# main.net
KiCad netlist of a schematic drawn in EAGLE
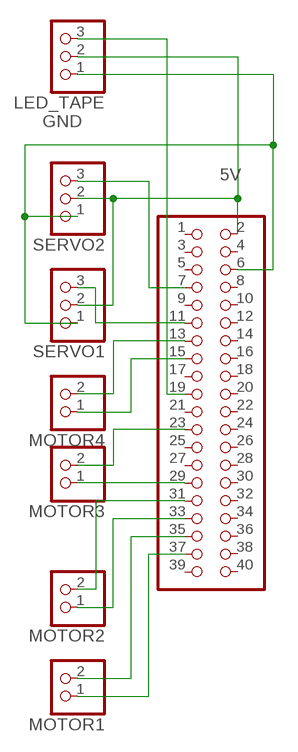
[diagram p0: schematic, sheet 1]

(export (version "E")
  (design (tool "Eeschema 10.0.6"))
  (components
    (comp (ref "JP")
      (value "PINHD-2X20")
      (footprint "eagle-import:2X20")
      (libsource (lib "eagle-import") (part "PINHD-2X20"))
    )
    (comp (ref "LED_TAPE")
      (value "PINHD-1X3")
      (footprint "eagle-import:1X03")
      (libsource (lib "eagle-import") (part "PINHD-1X3"))
    )
    (comp (ref "MOTOR1")
      (value "PINHD-1X2")
      (footprint "eagle-import:1X02")
      (libsource (lib "eagle-import") (part "PINHD-1X2"))
    )
    (comp (ref "MOTOR2")
      (value "PINHD-1X2")
      (footprint "eagle-import:1X02")
      (libsource (lib "eagle-import") (part "PINHD-1X2"))
    )
    (comp (ref "MOTOR3")
      (value "PINHD-1X2")
      (footprint "eagle-import:1X02")
      (libsource (lib "eagle-import") (part "PINHD-1X2"))
    )
    (comp (ref "MOTOR4")
      (value "PINHD-1X2")
      (footprint "eagle-import:1X02")
      (libsource (lib "eagle-import") (part "PINHD-1X2"))
    )
    (comp (ref "SERVO1")
      (value "PINHD-1X3")
      (footprint "eagle-import:1X03")
      (libsource (lib "eagle-import") (part "PINHD-1X3"))
    )
    (comp (ref "SERVO2")
      (value "PINHD-1X3")
      (footprint "eagle-import:1X03")
      (libsource (lib "eagle-import") (part "PINHD-1X3"))
    )
  )
  (nets
    (net (code "1") (name "/5V") (class "Default")
      (node (ref "JP") (pin "2") (pinfunction "2_2") (pintype "passive"))
      (node (ref "LED_TAPE") (pin "2") (pinfunction "2_2") (pintype "passive"))
      (node (ref "SERVO1") (pin "2") (pinfunction "2_2") (pintype "passive"))
      (node (ref "SERVO2") (pin "2") (pinfunction "2_2") (pintype "passive"))
    )
    (net (code "2") (name "/GND") (class "Default")
      (node (ref "JP") (pin "6") (pinfunction "6_6") (pintype "passive"))
      (node (ref "LED_TAPE") (pin "1") (pinfunction "1_1") (pintype "passive"))
      (node (ref "SERVO1") (pin "1") (pinfunction "1_1") (pintype "passive"))
      (node (ref "SERVO2") (pin "1") (pinfunction "1_1") (pintype "passive"))
    )
    (net (code "3") (name "Net-(JP-Pad7)") (class "Default")
      (node (ref "JP") (pin "7") (pinfunction "7_7") (pintype "passive"))
      (node (ref "SERVO2") (pin "3") (pinfunction "3_3") (pintype "passive"))
    )
    (net (code "4") (name "Net-(JP-Pad11)") (class "Default")
      (node (ref "JP") (pin "11") (pinfunction "11_11") (pintype "passive"))
      (node (ref "SERVO1") (pin "3") (pinfunction "3_3") (pintype "passive"))
    )
    (net (code "5") (name "Net-(JP-Pad13)") (class "Default")
      (node (ref "JP") (pin "13") (pinfunction "13_13") (pintype "passive"))
      (node (ref "MOTOR4") (pin "2") (pinfunction "2_2") (pintype "passive"))
    )
    (net (code "6") (name "Net-(JP-Pad15)") (class "Default")
      (node (ref "JP") (pin "15") (pinfunction "15_15") (pintype "passive"))
      (node (ref "MOTOR4") (pin "1") (pinfunction "1_1") (pintype "passive"))
    )
    (net (code "7") (name "Net-(JP-Pad19)") (class "Default")
      (node (ref "JP") (pin "19") (pinfunction "19_19") (pintype "passive"))
      (node (ref "LED_TAPE") (pin "3") (pinfunction "3_3") (pintype "passive"))
    )
    (net (code "8") (name "Net-(JP-Pad23)") (class "Default")
      (node (ref "JP") (pin "23") (pinfunction "23_23") (pintype "passive"))
      (node (ref "MOTOR3") (pin "2") (pinfunction "2_2") (pintype "passive"))
    )
    (net (code "9") (name "Net-(JP-Pad29)") (class "Default")
      (node (ref "JP") (pin "29") (pinfunction "29_29") (pintype "passive"))
      (node (ref "MOTOR3") (pin "1") (pinfunction "1_1") (pintype "passive"))
    )
    (net (code "10") (name "Net-(JP-Pad31)") (class "Default")
      (node (ref "JP") (pin "31") (pinfunction "31_31") (pintype "passive"))
      (node (ref "MOTOR2") (pin "2") (pinfunction "2_2") (pintype "passive"))
    )
    (net (code "11") (name "Net-(JP-Pad33)") (class "Default")
      (node (ref "JP") (pin "33") (pinfunction "33_33") (pintype "passive"))
      (node (ref "MOTOR2") (pin "1") (pinfunction "1_1") (pintype "passive"))
    )
    (net (code "12") (name "Net-(JP-Pad35)") (class "Default")
      (node (ref "JP") (pin "35") (pinfunction "35_35") (pintype "passive"))
      (node (ref "MOTOR1") (pin "2") (pinfunction "2_2") (pintype "passive"))
    )
    (net (code "13") (name "Net-(JP-Pad37)") (class "Default")
      (node (ref "JP") (pin "37") (pinfunction "37_37") (pintype "passive"))
      (node (ref "MOTOR1") (pin "1") (pinfunction "1_1") (pintype "passive"))
    )
    (net (code "14") (name "unconnected-(JP-Pad1)") (class "Default")
      (node (ref "JP") (pin "1") (pinfunction "1_1") (pintype "passive"))
    )
    (net (code "15") (name "unconnected-(JP-Pad3)") (class "Default")
      (node (ref "JP") (pin "3") (pinfunction "3_3") (pintype "passive"))
    )
    (net (code "16") (name "unconnected-(JP-Pad4)") (class "Default")
      (node (ref "JP") (pin "4") (pinfunction "4_4") (pintype "passive"))
    )
    (net (code "17") (name "unconnected-(JP-Pad5)") (class "Default")
      (node (ref "JP") (pin "5") (pinfunction "5_5") (pintype "passive"))
    )
    (net (code "18") (name "unconnected-(JP-Pad8)") (class "Default")
      (node (ref "JP") (pin "8") (pinfunction "8_8") (pintype "passive"))
    )
    (net (code "19") (name "unconnected-(JP-Pad9)") (class "Default")
      (node (ref "JP") (pin "9") (pinfunction "9_9") (pintype "passive"))
    )
    (net (code "20") (name "unconnected-(JP-Pad10)") (class "Default")
      (node (ref "JP") (pin "10") (pinfunction "10_10") (pintype "passive"))
    )
    (net (code "21") (name "unconnected-(JP-Pad12)") (class "Default")
      (node (ref "JP") (pin "12") (pinfunction "12_12") (pintype "passive"))
    )
    (net (code "22") (name "unconnected-(JP-Pad14)") (class "Default")
      (node (ref "JP") (pin "14") (pinfunction "14_14") (pintype "passive"))
    )
    (net (code "23") (name "unconnected-(JP-Pad16)") (class "Default")
      (node (ref "JP") (pin "16") (pinfunction "16_16") (pintype "passive"))
    )
    (net (code "24") (name "unconnected-(JP-Pad17)") (class "Default")
      (node (ref "JP") (pin "17") (pinfunction "17_17") (pintype "passive"))
    )
    (net (code "25") (name "unconnected-(JP-Pad18)") (class "Default")
      (node (ref "JP") (pin "18") (pinfunction "18_18") (pintype "passive"))
    )
    (net (code "26") (name "unconnected-(JP-Pad20)") (class "Default")
      (node (ref "JP") (pin "20") (pinfunction "20_20") (pintype "passive"))
    )
    (net (code "27") (name "unconnected-(JP-Pad21)") (class "Default")
      (node (ref "JP") (pin "21") (pinfunction "21_21") (pintype "passive"))
    )
    (net (code "28") (name "unconnected-(JP-Pad22)") (class "Default")
      (node (ref "JP") (pin "22") (pinfunction "22_22") (pintype "passive"))
    )
    (net (code "29") (name "unconnected-(JP-Pad24)") (class "Default")
      (node (ref "JP") (pin "24") (pinfunction "24_24") (pintype "passive"))
    )
    (net (code "30") (name "unconnected-(JP-Pad25)") (class "Default")
      (node (ref "JP") (pin "25") (pinfunction "25_25") (pintype "passive"))
    )
    (net (code "31") (name "unconnected-(JP-Pad26)") (class "Default")
      (node (ref "JP") (pin "26") (pinfunction "26_26") (pintype "passive"))
    )
    (net (code "32") (name "unconnected-(JP-Pad27)") (class "Default")
      (node (ref "JP") (pin "27") (pinfunction "27_27") (pintype "passive"))
    )
    (net (code "33") (name "unconnected-(JP-Pad28)") (class "Default")
      (node (ref "JP") (pin "28") (pinfunction "28_28") (pintype "passive"))
    )
    (net (code "34") (name "unconnected-(JP-Pad30)") (class "Default")
      (node (ref "JP") (pin "30") (pinfunction "30_30") (pintype "passive"))
    )
    (net (code "35") (name "unconnected-(JP-Pad32)") (class "Default")
      (node (ref "JP") (pin "32") (pinfunction "32_32") (pintype "passive"))
    )
    (net (code "36") (name "unconnected-(JP-Pad34)") (class "Default")
      (node (ref "JP") (pin "34") (pinfunction "34_34") (pintype "passive"))
    )
    (net (code "37") (name "unconnected-(JP-Pad36)") (class "Default")
      (node (ref "JP") (pin "36") (pinfunction "36_36") (pintype "passive"))
    )
    (net (code "38") (name "unconnected-(JP-Pad38)") (class "Default")
      (node (ref "JP") (pin "38") (pinfunction "38_38") (pintype "passive"))
    )
    (net (code "39") (name "unconnected-(JP-Pad39)") (class "Default")
      (node (ref "JP") (pin "39") (pinfunction "39_39") (pintype "passive"))
    )
    (net (code "40") (name "unconnected-(JP-Pad40)") (class "Default")
      (node (ref "JP") (pin "40") (pinfunction "40_40") (pintype "passive"))
    )
  )
)
